# bot_schem_rev10_3.net
KiCad netlist of a schematic drawn in Altium Designer
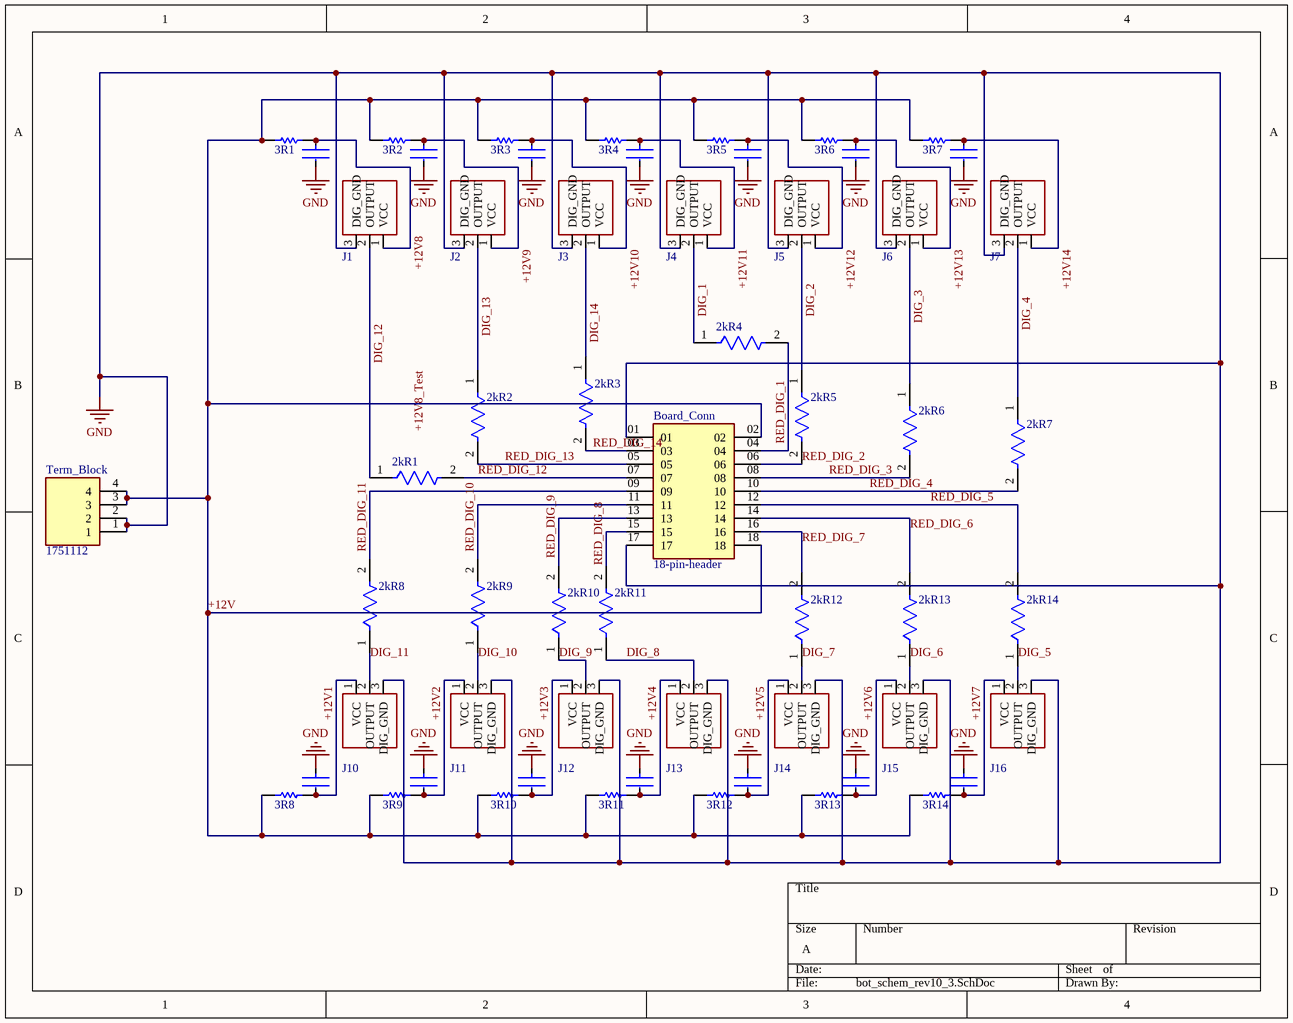
[diagram p0: bot_schem_rev10_3.SchDoc]

(export (version "E")
  (design (tool "Eeschema 10.0.6"))
  (components
    (comp (ref "2kR1")
      (value "CRCW06031K80FKEA")
      (footprint "2kOhm")
      (description "Res Thick Film 0603 1.8K Ohm 1% 1/10W ±100ppm/°C Molded SMD Paper T/R")
      (fields (field (name "MANUFACTURER") "Vishay") (field (name "TOLERANCE") "1%"))
      (libsource (lib "bot_schlib") (part "CRCW06031K80FKEA"))
    )
    (comp (ref "2kR2")
      (value "CRCW06031K80FKEA")
      (footprint "2kOhm")
      (description "Res Thick Film 0603 1.8K Ohm 1% 1/10W ±100ppm/°C Molded SMD Paper T/R")
      (fields (field (name "MANUFACTURER") "Vishay") (field (name "TOLERANCE") "1%"))
      (libsource (lib "bot_schlib") (part "CRCW06031K80FKEA"))
    )
    (comp (ref "2kR3")
      (value "CRCW06031K80FKEA")
      (footprint "2kOhm")
      (description "Res Thick Film 0603 1.8K Ohm 1% 1/10W ±100ppm/°C Molded SMD Paper T/R")
      (fields (field (name "MANUFACTURER") "Vishay") (field (name "TOLERANCE") "1%"))
      (libsource (lib "bot_schlib") (part "CRCW06031K80FKEA"))
    )
    (comp (ref "2kR4")
      (value "CRCW06031K80FKEA")
      (footprint "2kOhm")
      (description "Res Thick Film 0603 1.8K Ohm 1% 1/10W ±100ppm/°C Molded SMD Paper T/R")
      (fields (field (name "MANUFACTURER") "Vishay") (field (name "TOLERANCE") "1%"))
      (libsource (lib "bot_schlib") (part "CRCW06031K80FKEA"))
    )
    (comp (ref "2kR5")
      (value "CRCW06031K80FKEA")
      (footprint "2kOhm")
      (description "Res Thick Film 0603 1.8K Ohm 1% 1/10W ±100ppm/°C Molded SMD Paper T/R")
      (fields (field (name "MANUFACTURER") "Vishay") (field (name "TOLERANCE") "1%"))
      (libsource (lib "bot_schlib") (part "CRCW06031K80FKEA"))
    )
    (comp (ref "2kR6")
      (value "CRCW06031K80FKEA")
      (footprint "2kOhm")
      (description "Res Thick Film 0603 1.8K Ohm 1% 1/10W ±100ppm/°C Molded SMD Paper T/R")
      (fields (field (name "MANUFACTURER") "Vishay") (field (name "TOLERANCE") "1%"))
      (libsource (lib "bot_schlib") (part "CRCW06031K80FKEA"))
    )
    (comp (ref "2kR7")
      (value "CRCW06031K80FKEA")
      (footprint "2kOhm")
      (description "Res Thick Film 0603 1.8K Ohm 1% 1/10W ±100ppm/°C Molded SMD Paper T/R")
      (fields (field (name "MANUFACTURER") "Vishay") (field (name "TOLERANCE") "1%"))
      (libsource (lib "bot_schlib") (part "CRCW06031K80FKEA"))
    )
    (comp (ref "2kR8")
      (value "CRCW06031K80FKEA")
      (footprint "2kOhm")
      (description "Res Thick Film 0603 1.8K Ohm 1% 1/10W ±100ppm/°C Molded SMD Paper T/R")
      (fields (field (name "MANUFACTURER") "Vishay") (field (name "TOLERANCE") "1%"))
      (libsource (lib "bot_schlib") (part "CRCW06031K80FKEA"))
    )
    (comp (ref "2kR9")
      (value "CRCW06031K80FKEA")
      (footprint "2kOhm")
      (description "Res Thick Film 0603 1.8K Ohm 1% 1/10W ±100ppm/°C Molded SMD Paper T/R")
      (fields (field (name "MANUFACTURER") "Vishay") (field (name "TOLERANCE") "1%"))
      (libsource (lib "bot_schlib") (part "CRCW06031K80FKEA"))
    )
    (comp (ref "2kR10")
      (value "CRCW06031K80FKEA")
      (footprint "2kOhm")
      (description "Res Thick Film 0603 1.8K Ohm 1% 1/10W ±100ppm/°C Molded SMD Paper T/R")
      (fields (field (name "MANUFACTURER") "Vishay") (field (name "TOLERANCE") "1%"))
      (libsource (lib "bot_schlib") (part "CRCW06031K80FKEA"))
    )
    (comp (ref "2kR11")
      (value "CRCW06031K80FKEA")
      (footprint "2kOhm")
      (description "Res Thick Film 0603 1.8K Ohm 1% 1/10W ±100ppm/°C Molded SMD Paper T/R")
      (fields (field (name "MANUFACTURER") "Vishay") (field (name "TOLERANCE") "1%"))
      (libsource (lib "bot_schlib") (part "CRCW06031K80FKEA"))
    )
    (comp (ref "2kR12")
      (value "CRCW06031K80FKEA")
      (footprint "2kOhm")
      (description "Res Thick Film 0603 1.8K Ohm 1% 1/10W ±100ppm/°C Molded SMD Paper T/R")
      (fields (field (name "MANUFACTURER") "Vishay") (field (name "TOLERANCE") "1%"))
      (libsource (lib "bot_schlib") (part "CRCW06031K80FKEA"))
    )
    (comp (ref "2kR13")
      (value "CRCW06031K80FKEA")
      (footprint "2kOhm")
      (description "Res Thick Film 0603 1.8K Ohm 1% 1/10W ±100ppm/°C Molded SMD Paper T/R")
      (fields (field (name "MANUFACTURER") "Vishay") (field (name "TOLERANCE") "1%"))
      (libsource (lib "bot_schlib") (part "CRCW06031K80FKEA"))
    )
    (comp (ref "2kR14")
      (value "CRCW06031K80FKEA")
      (footprint "2kOhm")
      (description "Res Thick Film 0603 1.8K Ohm 1% 1/10W ±100ppm/°C Molded SMD Paper T/R")
      (fields (field (name "MANUFACTURER") "Vishay") (field (name "TOLERANCE") "1%"))
      (libsource (lib "bot_schlib") (part "CRCW06031K80FKEA"))
    )
    (comp (ref "3R1")
      (value "ERJ-8GEYJ3R0V")
      (footprint "3 ohm")
      (description "Res Thick Film 1206 3 Ohm 5% 1/4W -100ppm/C to 600ppm/C Molded SMD Punched Carrier T/R")
      (fields (field (name "MANUFACTURER") "Panasonic") (field (name "TOLERANCE") "5%"))
      (libsource (lib "bot_schlib") (part "ERJ-8GEYJ3R0V"))
    )
    (comp (ref "3R2")
      (value "ERJ-8GEYJ3R0V")
      (footprint "3 ohm")
      (description "Res Thick Film 1206 3 Ohm 5% 1/4W -100ppm/C to 600ppm/C Molded SMD Punched Carrier T/R")
      (fields (field (name "MANUFACTURER") "Panasonic") (field (name "TOLERANCE") "5%"))
      (libsource (lib "bot_schlib") (part "ERJ-8GEYJ3R0V"))
    )
    (comp (ref "3R3")
      (value "ERJ-8GEYJ3R0V")
      (footprint "3 ohm")
      (description "Res Thick Film 1206 3 Ohm 5% 1/4W -100ppm/C to 600ppm/C Molded SMD Punched Carrier T/R")
      (fields (field (name "MANUFACTURER") "Panasonic") (field (name "TOLERANCE") "5%"))
      (libsource (lib "bot_schlib") (part "ERJ-8GEYJ3R0V"))
    )
    (comp (ref "3R4")
      (value "ERJ-8GEYJ3R0V")
      (footprint "3 ohm")
      (description "Res Thick Film 1206 3 Ohm 5% 1/4W -100ppm/C to 600ppm/C Molded SMD Punched Carrier T/R")
      (fields (field (name "MANUFACTURER") "Panasonic") (field (name "TOLERANCE") "5%"))
      (libsource (lib "bot_schlib") (part "ERJ-8GEYJ3R0V"))
    )
    (comp (ref "3R5")
      (value "ERJ-8GEYJ3R0V")
      (footprint "3 ohm")
      (description "Res Thick Film 1206 3 Ohm 5% 1/4W -100ppm/C to 600ppm/C Molded SMD Punched Carrier T/R")
      (fields (field (name "MANUFACTURER") "Panasonic") (field (name "TOLERANCE") "5%"))
      (libsource (lib "bot_schlib") (part "ERJ-8GEYJ3R0V"))
    )
    (comp (ref "3R6")
      (value "ERJ-8GEYJ3R0V")
      (footprint "3 ohm")
      (description "Res Thick Film 1206 3 Ohm 5% 1/4W -100ppm/C to 600ppm/C Molded SMD Punched Carrier T/R")
      (fields (field (name "MANUFACTURER") "Panasonic") (field (name "TOLERANCE") "5%"))
      (libsource (lib "bot_schlib") (part "ERJ-8GEYJ3R0V"))
    )
    (comp (ref "3R7")
      (value "ERJ-8GEYJ3R0V")
      (footprint "3 ohm")
      (description "Res Thick Film 1206 3 Ohm 5% 1/4W -100ppm/C to 600ppm/C Molded SMD Punched Carrier T/R")
      (fields (field (name "MANUFACTURER") "Panasonic") (field (name "TOLERANCE") "5%"))
      (libsource (lib "bot_schlib") (part "ERJ-8GEYJ3R0V"))
    )
    (comp (ref "3R8")
      (value "ERJ-8GEYJ3R0V")
      (footprint "3 ohm")
      (description "Res Thick Film 1206 3 Ohm 5% 1/4W -100ppm/C to 600ppm/C Molded SMD Punched Carrier T/R")
      (fields (field (name "MANUFACTURER") "Panasonic") (field (name "TOLERANCE") "5%"))
      (libsource (lib "bot_schlib") (part "ERJ-8GEYJ3R0V"))
    )
    (comp (ref "3R9")
      (value "ERJ-8GEYJ3R0V")
      (footprint "3 ohm")
      (description "Res Thick Film 1206 3 Ohm 5% 1/4W -100ppm/C to 600ppm/C Molded SMD Punched Carrier T/R")
      (fields (field (name "MANUFACTURER") "Panasonic") (field (name "TOLERANCE") "5%"))
      (libsource (lib "bot_schlib") (part "ERJ-8GEYJ3R0V"))
    )
    (comp (ref "3R10")
      (value "ERJ-8GEYJ3R0V")
      (footprint "3 ohm")
      (description "Res Thick Film 1206 3 Ohm 5% 1/4W -100ppm/C to 600ppm/C Molded SMD Punched Carrier T/R")
      (fields (field (name "MANUFACTURER") "Panasonic") (field (name "TOLERANCE") "5%"))
      (libsource (lib "bot_schlib") (part "ERJ-8GEYJ3R0V"))
    )
    (comp (ref "3R11")
      (value "ERJ-8GEYJ3R0V")
      (footprint "3 ohm")
      (description "Res Thick Film 1206 3 Ohm 5% 1/4W -100ppm/C to 600ppm/C Molded SMD Punched Carrier T/R")
      (fields (field (name "MANUFACTURER") "Panasonic") (field (name "TOLERANCE") "5%"))
      (libsource (lib "bot_schlib") (part "ERJ-8GEYJ3R0V"))
    )
    (comp (ref "3R12")
      (value "ERJ-8GEYJ3R0V")
      (footprint "3 ohm")
      (description "Res Thick Film 1206 3 Ohm 5% 1/4W -100ppm/C to 600ppm/C Molded SMD Punched Carrier T/R")
      (fields (field (name "MANUFACTURER") "Panasonic") (field (name "TOLERANCE") "5%"))
      (libsource (lib "bot_schlib") (part "ERJ-8GEYJ3R0V"))
    )
    (comp (ref "3R13")
      (value "ERJ-8GEYJ3R0V")
      (footprint "3 ohm")
      (description "Res Thick Film 1206 3 Ohm 5% 1/4W -100ppm/C to 600ppm/C Molded SMD Punched Carrier T/R")
      (fields (field (name "MANUFACTURER") "Panasonic") (field (name "TOLERANCE") "5%"))
      (libsource (lib "bot_schlib") (part "ERJ-8GEYJ3R0V"))
    )
    (comp (ref "3R14")
      (value "ERJ-8GEYJ3R0V")
      (footprint "3 ohm")
      (description "Res Thick Film 1206 3 Ohm 5% 1/4W -100ppm/C to 600ppm/C Molded SMD Punched Carrier T/R")
      (fields (field (name "MANUFACTURER") "Panasonic") (field (name "TOLERANCE") "5%"))
      (libsource (lib "bot_schlib") (part "ERJ-8GEYJ3R0V"))
    )
    (comp (ref "Board_Conn")
      (value "18-pin-header")
      (footprint "18 pin header")
      (libsource (lib "bot_schlib") (part "18-pin-header"))
    )
    (comp (ref "C1")
      (value "C0805C104K5RACTU")
      (footprint "100nF")
      (description "Cap Ceramic 0.1uF 50V X7R 10% SMD 2.0 x 1.2 mm 125 C Paper T/R")
      (fields (field (name "MANUFACTURER") "KEMET") (field (name "TOLERANCE") "10%"))
      (libsource (lib "bot_schlib") (part "C0805C104K5RACTU"))
    )
    (comp (ref "C2")
      (value "C0805C104K5RACTU")
      (footprint "100nF")
      (description "Cap Ceramic 0.1uF 50V X7R 10% SMD 2.0 x 1.2 mm 125 C Paper T/R")
      (fields (field (name "MANUFACTURER") "KEMET") (field (name "TOLERANCE") "10%"))
      (libsource (lib "bot_schlib") (part "C0805C104K5RACTU"))
    )
    (comp (ref "C3")
      (value "C0805C104K5RACTU")
      (footprint "100nF")
      (description "Cap Ceramic 0.1uF 50V X7R 10% SMD 2.0 x 1.2 mm 125 C Paper T/R")
      (fields (field (name "MANUFACTURER") "KEMET") (field (name "TOLERANCE") "10%"))
      (libsource (lib "bot_schlib") (part "C0805C104K5RACTU"))
    )
    (comp (ref "C4")
      (value "C0805C104K5RACTU")
      (footprint "100nF")
      (description "Cap Ceramic 0.1uF 50V X7R 10% SMD 2.0 x 1.2 mm 125 C Paper T/R")
      (fields (field (name "MANUFACTURER") "KEMET") (field (name "TOLERANCE") "10%"))
      (libsource (lib "bot_schlib") (part "C0805C104K5RACTU"))
    )
    (comp (ref "C5")
      (value "C0805C104K5RACTU")
      (footprint "100nF")
      (description "Cap Ceramic 0.1uF 50V X7R 10% SMD 2.0 x 1.2 mm 125 C Paper T/R")
      (fields (field (name "MANUFACTURER") "KEMET") (field (name "TOLERANCE") "10%"))
      (libsource (lib "bot_schlib") (part "C0805C104K5RACTU"))
    )
    (comp (ref "C6")
      (value "C0805C104K5RACTU")
      (footprint "100nF")
      (description "Cap Ceramic 0.1uF 50V X7R 10% SMD 2.0 x 1.2 mm 125 C Paper T/R")
      (fields (field (name "MANUFACTURER") "KEMET") (field (name "TOLERANCE") "10%"))
      (libsource (lib "bot_schlib") (part "C0805C104K5RACTU"))
    )
    (comp (ref "C7")
      (value "C0805C104K5RACTU")
      (footprint "100nF")
      (description "Cap Ceramic 0.1uF 50V X7R 10% SMD 2.0 x 1.2 mm 125 C Paper T/R")
      (fields (field (name "MANUFACTURER") "KEMET") (field (name "TOLERANCE") "10%"))
      (libsource (lib "bot_schlib") (part "C0805C104K5RACTU"))
    )
    (comp (ref "C8")
      (value "C0805C104K5RACTU")
      (footprint "100nF")
      (description "Cap Ceramic 0.1uF 50V X7R 10% SMD 2.0 x 1.2 mm 125 C Paper T/R")
      (fields (field (name "MANUFACTURER") "KEMET") (field (name "TOLERANCE") "10%"))
      (libsource (lib "bot_schlib") (part "C0805C104K5RACTU"))
    )
    (comp (ref "C9")
      (value "C0805C104K5RACTU")
      (footprint "100nF")
      (description "Cap Ceramic 0.1uF 50V X7R 10% SMD 2.0 x 1.2 mm 125 C Paper T/R")
      (fields (field (name "MANUFACTURER") "KEMET") (field (name "TOLERANCE") "10%"))
      (libsource (lib "bot_schlib") (part "C0805C104K5RACTU"))
    )
    (comp (ref "C10")
      (value "C0805C104K5RACTU")
      (footprint "100nF")
      (description "Cap Ceramic 0.1uF 50V X7R 10% SMD 2.0 x 1.2 mm 125 C Paper T/R")
      (fields (field (name "MANUFACTURER") "KEMET") (field (name "TOLERANCE") "10%"))
      (libsource (lib "bot_schlib") (part "C0805C104K5RACTU"))
    )
    (comp (ref "C11")
      (value "C0805C104K5RACTU")
      (footprint "100nF")
      (description "Cap Ceramic 0.1uF 50V X7R 10% SMD 2.0 x 1.2 mm 125 C Paper T/R")
      (fields (field (name "MANUFACTURER") "KEMET") (field (name "TOLERANCE") "10%"))
      (libsource (lib "bot_schlib") (part "C0805C104K5RACTU"))
    )
    (comp (ref "C12")
      (value "C0805C104K5RACTU")
      (footprint "100nF")
      (description "Cap Ceramic 0.1uF 50V X7R 10% SMD 2.0 x 1.2 mm 125 C Paper T/R")
      (fields (field (name "MANUFACTURER") "KEMET") (field (name "TOLERANCE") "10%"))
      (libsource (lib "bot_schlib") (part "C0805C104K5RACTU"))
    )
    (comp (ref "C13")
      (value "C0805C104K5RACTU")
      (footprint "100nF")
      (description "Cap Ceramic 0.1uF 50V X7R 10% SMD 2.0 x 1.2 mm 125 C Paper T/R")
      (fields (field (name "MANUFACTURER") "KEMET") (field (name "TOLERANCE") "10%"))
      (libsource (lib "bot_schlib") (part "C0805C104K5RACTU"))
    )
    (comp (ref "C14")
      (value "C0805C104K5RACTU")
      (footprint "100nF")
      (description "Cap Ceramic 0.1uF 50V X7R 10% SMD 2.0 x 1.2 mm 125 C Paper T/R")
      (fields (field (name "MANUFACTURER") "KEMET") (field (name "TOLERANCE") "10%"))
      (libsource (lib "bot_schlib") (part "C0805C104K5RACTU"))
    )
    (comp (ref "J1")
      (value "IF-D95T")
      (footprint "IF-D95")
      (description "DETECTOR PHOTOLOGIC TTL/CMOS")
      (fields (field (name "MANUFACTURER") "Industrial Fiber Optics"))
      (libsource (lib "bot_schlib") (part "IF-D95T"))
    )
    (comp (ref "J2")
      (value "IF-D95T")
      (footprint "IF-D95")
      (description "DETECTOR PHOTOLOGIC TTL/CMOS")
      (fields (field (name "MANUFACTURER") "Industrial Fiber Optics"))
      (libsource (lib "bot_schlib") (part "IF-D95T"))
    )
    (comp (ref "J3")
      (value "IF-D95T")
      (footprint "IF-D95")
      (description "DETECTOR PHOTOLOGIC TTL/CMOS")
      (fields (field (name "MANUFACTURER") "Industrial Fiber Optics"))
      (libsource (lib "bot_schlib") (part "IF-D95T"))
    )
    (comp (ref "J4")
      (value "IF-D95T")
      (footprint "IF-D95")
      (description "DETECTOR PHOTOLOGIC TTL/CMOS")
      (fields (field (name "MANUFACTURER") "Industrial Fiber Optics"))
      (libsource (lib "bot_schlib") (part "IF-D95T"))
    )
    (comp (ref "J5")
      (value "IF-D95T")
      (footprint "IF-D95")
      (description "DETECTOR PHOTOLOGIC TTL/CMOS")
      (fields (field (name "MANUFACTURER") "Industrial Fiber Optics"))
      (libsource (lib "bot_schlib") (part "IF-D95T"))
    )
    (comp (ref "J6")
      (value "IF-D95T")
      (footprint "IF-D95")
      (description "DETECTOR PHOTOLOGIC TTL/CMOS")
      (fields (field (name "MANUFACTURER") "Industrial Fiber Optics"))
      (libsource (lib "bot_schlib") (part "IF-D95T"))
    )
    (comp (ref "J7")
      (value "IF-D95T")
      (footprint "IF-D95")
      (description "DETECTOR PHOTOLOGIC TTL/CMOS")
      (fields (field (name "MANUFACTURER") "Industrial Fiber Optics"))
      (libsource (lib "bot_schlib") (part "IF-D95T"))
    )
    (comp (ref "J10")
      (value "IF-D95T")
      (footprint "IF-D95")
      (description "DETECTOR PHOTOLOGIC TTL/CMOS")
      (fields (field (name "MANUFACTURER") "Industrial Fiber Optics"))
      (libsource (lib "bot_schlib") (part "IF-D95T"))
    )
    (comp (ref "J11")
      (value "IF-D95T")
      (footprint "IF-D95")
      (description "DETECTOR PHOTOLOGIC TTL/CMOS")
      (fields (field (name "MANUFACTURER") "Industrial Fiber Optics"))
      (libsource (lib "bot_schlib") (part "IF-D95T"))
    )
    (comp (ref "J12")
      (value "IF-D95T")
      (footprint "IF-D95")
      (description "DETECTOR PHOTOLOGIC TTL/CMOS")
      (fields (field (name "MANUFACTURER") "Industrial Fiber Optics"))
      (libsource (lib "bot_schlib") (part "IF-D95T"))
    )
    (comp (ref "J13")
      (value "IF-D95T")
      (footprint "IF-D95")
      (description "DETECTOR PHOTOLOGIC TTL/CMOS")
      (fields (field (name "MANUFACTURER") "Industrial Fiber Optics"))
      (libsource (lib "bot_schlib") (part "IF-D95T"))
    )
    (comp (ref "J14")
      (value "IF-D95T")
      (footprint "IF-D95")
      (description "DETECTOR PHOTOLOGIC TTL/CMOS")
      (fields (field (name "MANUFACTURER") "Industrial Fiber Optics"))
      (libsource (lib "bot_schlib") (part "IF-D95T"))
    )
    (comp (ref "J15")
      (value "IF-D95T")
      (footprint "IF-D95")
      (description "DETECTOR PHOTOLOGIC TTL/CMOS")
      (fields (field (name "MANUFACTURER") "Industrial Fiber Optics"))
      (libsource (lib "bot_schlib") (part "IF-D95T"))
    )
    (comp (ref "J16")
      (value "IF-D95T")
      (footprint "IF-D95")
      (description "DETECTOR PHOTOLOGIC TTL/CMOS")
      (fields (field (name "MANUFACTURER") "Industrial Fiber Optics"))
      (libsource (lib "bot_schlib") (part "IF-D95T"))
    )
    (comp (ref "Term_Block")
      (value "1751112")
      (footprint "4-pin terminal HORIZONTAL")
      (libsource (lib "bot_schlib") (part "1751112"))
    )
  )
  (nets
    (net (code "1") (name "/+12V") (class "Default")
      (node (ref "3R1") (pin "1") (pinfunction "1_1") (pintype "passive"))
      (node (ref "3R10") (pin "1") (pinfunction "1_1") (pintype "passive"))
      (node (ref "3R11") (pin "1") (pinfunction "1_1") (pintype "passive"))
      (node (ref "3R12") (pin "1") (pinfunction "1_1") (pintype "passive"))
      (node (ref "3R13") (pin "1") (pinfunction "1_1") (pintype "passive"))
      (node (ref "3R14") (pin "1") (pinfunction "1_1") (pintype "passive"))
      (node (ref "3R2") (pin "1") (pinfunction "1_1") (pintype "passive"))
      (node (ref "3R3") (pin "1") (pinfunction "1_1") (pintype "passive"))
      (node (ref "3R4") (pin "1") (pinfunction "1_1") (pintype "passive"))
      (node (ref "3R5") (pin "1") (pinfunction "1_1") (pintype "passive"))
      (node (ref "3R6") (pin "1") (pinfunction "1_1") (pintype "passive"))
      (node (ref "3R7") (pin "1") (pinfunction "1_1") (pintype "passive"))
      (node (ref "3R8") (pin "1") (pinfunction "1_1") (pintype "passive"))
      (node (ref "3R9") (pin "1") (pinfunction "1_1") (pintype "passive"))
      (node (ref "Board_Conn") (pin "02") (pinfunction "02_02") (pintype "passive"))
      (node (ref "Board_Conn") (pin "18") (pinfunction "18_18") (pintype "passive"))
      (node (ref "Term_Block") (pin "3") (pinfunction "3_3") (pintype "passive"))
      (node (ref "Term_Block") (pin "4") (pinfunction "4_4") (pintype "passive"))
    )
    (net (code "2") (name "/+12V1") (class "Default")
      (node (ref "3R8") (pin "2") (pinfunction "2_2") (pintype "passive"))
      (node (ref "C8") (pin "2") (pinfunction "2_2") (pintype "passive"))
      (node (ref "J10") (pin "1") (pinfunction "VCC_1") (pintype "passive"))
    )
    (net (code "3") (name "/+12V2") (class "Default")
      (node (ref "3R9") (pin "2") (pinfunction "2_2") (pintype "passive"))
      (node (ref "C9") (pin "2") (pinfunction "2_2") (pintype "passive"))
      (node (ref "J11") (pin "1") (pinfunction "VCC_1") (pintype "passive"))
    )
    (net (code "4") (name "/+12V3") (class "Default")
      (node (ref "3R10") (pin "2") (pinfunction "2_2") (pintype "passive"))
      (node (ref "C10") (pin "2") (pinfunction "2_2") (pintype "passive"))
      (node (ref "J12") (pin "1") (pinfunction "VCC_1") (pintype "passive"))
    )
    (net (code "5") (name "/+12V4") (class "Default")
      (node (ref "3R11") (pin "2") (pinfunction "2_2") (pintype "passive"))
      (node (ref "C11") (pin "2") (pinfunction "2_2") (pintype "passive"))
      (node (ref "J13") (pin "1") (pinfunction "VCC_1") (pintype "passive"))
    )
    (net (code "6") (name "/+12V5") (class "Default")
      (node (ref "3R12") (pin "2") (pinfunction "2_2") (pintype "passive"))
      (node (ref "C12") (pin "2") (pinfunction "2_2") (pintype "passive"))
      (node (ref "J14") (pin "1") (pinfunction "VCC_1") (pintype "passive"))
    )
    (net (code "7") (name "/+12V6") (class "Default")
      (node (ref "3R13") (pin "2") (pinfunction "2_2") (pintype "passive"))
      (node (ref "C13") (pin "2") (pinfunction "2_2") (pintype "passive"))
      (node (ref "J15") (pin "1") (pinfunction "VCC_1") (pintype "passive"))
    )
    (net (code "8") (name "/+12V7") (class "Default")
      (node (ref "3R14") (pin "2") (pinfunction "2_2") (pintype "passive"))
      (node (ref "C14") (pin "2") (pinfunction "2_2") (pintype "passive"))
      (node (ref "J16") (pin "1") (pinfunction "VCC_1") (pintype "passive"))
    )
    (net (code "9") (name "/+12V8") (class "Default")
      (node (ref "3R1") (pin "2") (pinfunction "2_2") (pintype "passive"))
      (node (ref "C1") (pin "1") (pinfunction "1_1") (pintype "passive"))
      (node (ref "J1") (pin "1") (pinfunction "VCC_1") (pintype "passive"))
    )
    (net (code "11") (name "/+12V9") (class "Default")
      (node (ref "3R2") (pin "2") (pinfunction "2_2") (pintype "passive"))
      (node (ref "C2") (pin "1") (pinfunction "1_1") (pintype "passive"))
      (node (ref "J2") (pin "1") (pinfunction "VCC_1") (pintype "passive"))
    )
    (net (code "12") (name "/+12V10") (class "Default")
      (node (ref "3R3") (pin "2") (pinfunction "2_2") (pintype "passive"))
      (node (ref "C3") (pin "1") (pinfunction "1_1") (pintype "passive"))
      (node (ref "J3") (pin "1") (pinfunction "VCC_1") (pintype "passive"))
    )
    (net (code "13") (name "/+12V11") (class "Default")
      (node (ref "3R4") (pin "2") (pinfunction "2_2") (pintype "passive"))
      (node (ref "C4") (pin "1") (pinfunction "1_1") (pintype "passive"))
      (node (ref "J4") (pin "1") (pinfunction "VCC_1") (pintype "passive"))
    )
    (net (code "14") (name "/+12V12") (class "Default")
      (node (ref "3R5") (pin "2") (pinfunction "2_2") (pintype "passive"))
      (node (ref "C5") (pin "1") (pinfunction "1_1") (pintype "passive"))
      (node (ref "J5") (pin "1") (pinfunction "VCC_1") (pintype "passive"))
    )
    (net (code "15") (name "/+12V13") (class "Default")
      (node (ref "3R6") (pin "2") (pinfunction "2_2") (pintype "passive"))
      (node (ref "C6") (pin "1") (pinfunction "1_1") (pintype "passive"))
      (node (ref "J6") (pin "1") (pinfunction "VCC_1") (pintype "passive"))
    )
    (net (code "16") (name "/+12V14") (class "Default")
      (node (ref "3R7") (pin "2") (pinfunction "2_2") (pintype "passive"))
      (node (ref "C7") (pin "1") (pinfunction "1_1") (pintype "passive"))
      (node (ref "J7") (pin "1") (pinfunction "VCC_1") (pintype "passive"))
    )
    (net (code "17") (name "/DIG_1") (class "Default")
      (node (ref "2kR4") (pin "1") (pinfunction "1_1") (pintype "passive"))
      (node (ref "J4") (pin "2") (pinfunction "OUTPUT_2") (pintype "passive"))
    )
    (net (code "18") (name "/DIG_2") (class "Default")
      (node (ref "2kR5") (pin "1") (pinfunction "1_1") (pintype "passive"))
      (node (ref "J5") (pin "2") (pinfunction "OUTPUT_2") (pintype "passive"))
    )
    (net (code "19") (name "/DIG_3") (class "Default")
      (node (ref "2kR6") (pin "1") (pinfunction "1_1") (pintype "passive"))
      (node (ref "J6") (pin "2") (pinfunction "OUTPUT_2") (pintype "passive"))
    )
    (net (code "20") (name "/DIG_4") (class "Default")
      (node (ref "2kR7") (pin "1") (pinfunction "1_1") (pintype "passive"))
      (node (ref "J7") (pin "2") (pinfunction "OUTPUT_2") (pintype "passive"))
    )
    (net (code "24") (name "/DIG_8") (class "Default")
      (node (ref "2kR11") (pin "1") (pinfunction "1_1") (pintype "passive"))
      (node (ref "J13") (pin "2") (pinfunction "OUTPUT_2") (pintype "passive"))
    )
    (net (code "25") (name "/DIG_9") (class "Default")
      (node (ref "2kR10") (pin "1") (pinfunction "1_1") (pintype "passive"))
      (node (ref "J12") (pin "2") (pinfunction "OUTPUT_2") (pintype "passive"))
    )
    (net (code "26") (name "/DIG_10") (class "Default")
      (node (ref "2kR9") (pin "1") (pinfunction "1_1") (pintype "passive"))
      (node (ref "J11") (pin "2") (pinfunction "OUTPUT_2") (pintype "passive"))
    )
    (net (code "27") (name "/DIG_11") (class "Default")
      (node (ref "2kR8") (pin "1") (pinfunction "1_1") (pintype "passive"))
      (node (ref "J10") (pin "2") (pinfunction "OUTPUT_2") (pintype "passive"))
    )
    (net (code "28") (name "/DIG_12") (class "Default")
      (node (ref "2kR1") (pin "1") (pinfunction "1_1") (pintype "passive"))
      (node (ref "J1") (pin "2") (pinfunction "OUTPUT_2") (pintype "passive"))
    )
    (net (code "29") (name "/DIG_13") (class "Default")
      (node (ref "2kR2") (pin "1") (pinfunction "1_1") (pintype "passive"))
      (node (ref "J2") (pin "2") (pinfunction "OUTPUT_2") (pintype "passive"))
    )
    (net (code "30") (name "/DIG_14") (class "Default")
      (node (ref "2kR3") (pin "1") (pinfunction "1_1") (pintype "passive"))
      (node (ref "J3") (pin "2") (pinfunction "OUTPUT_2") (pintype "passive"))
    )
    (net (code "31") (name "/RED_DIG_1") (class "Default")
      (node (ref "2kR4") (pin "2") (pinfunction "2_2") (pintype "passive"))
      (node (ref "Board_Conn") (pin "04") (pinfunction "04_04") (pintype "passive"))
    )
    (net (code "32") (name "/RED_DIG_2") (class "Default")
      (node (ref "2kR5") (pin "2") (pinfunction "2_2") (pintype "passive"))
      (node (ref "Board_Conn") (pin "06") (pinfunction "06_06") (pintype "passive"))
    )
    (net (code "33") (name "/RED_DIG_3") (class "Default")
      (node (ref "2kR6") (pin "2") (pinfunction "2_2") (pintype "passive"))
      (node (ref "Board_Conn") (pin "08") (pinfunction "08_08") (pintype "passive"))
    )
    (net (code "34") (name "/RED_DIG_4") (class "Default")
      (node (ref "2kR7") (pin "2") (pinfunction "2_2") (pintype "passive"))
      (node (ref "Board_Conn") (pin "10") (pinfunction "10_10") (pintype "passive"))
    )
    (net (code "35") (name "/RED_DIG_5") (class "Default")
      (node (ref "2kR14") (pin "2") (pinfunction "2_2") (pintype "passive"))
      (node (ref "Board_Conn") (pin "12") (pinfunction "12_12") (pintype "passive"))
    )
    (net (code "36") (name "/RED_DIG_6") (class "Default")
      (node (ref "2kR13") (pin "2") (pinfunction "2_2") (pintype "passive"))
      (node (ref "Board_Conn") (pin "14") (pinfunction "14_14") (pintype "passive"))
    )
    (net (code "37") (name "/RED_DIG_7") (class "Default")
      (node (ref "2kR12") (pin "2") (pinfunction "2_2") (pintype "passive"))
      (node (ref "Board_Conn") (pin "16") (pinfunction "16_16") (pintype "passive"))
    )
    (net (code "38") (name "/RED_DIG_8") (class "Default")
      (node (ref "2kR11") (pin "2") (pinfunction "2_2") (pintype "passive"))
      (node (ref "Board_Conn") (pin "15") (pinfunction "15_15") (pintype "passive"))
    )
    (net (code "39") (name "/RED_DIG_9") (class "Default")
      (node (ref "2kR10") (pin "2") (pinfunction "2_2") (pintype "passive"))
      (node (ref "Board_Conn") (pin "13") (pinfunction "13_13") (pintype "passive"))
    )
    (net (code "40") (name "/RED_DIG_10") (class "Default")
      (node (ref "2kR9") (pin "2") (pinfunction "2_2") (pintype "passive"))
      (node (ref "Board_Conn") (pin "11") (pinfunction "11_11") (pintype "passive"))
    )
    (net (code "41") (name "/RED_DIG_11") (class "Default")
      (node (ref "2kR8") (pin "2") (pinfunction "2_2") (pintype "passive"))
      (node (ref "Board_Conn") (pin "09") (pinfunction "09_09") (pintype "passive"))
    )
    (net (code "42") (name "/RED_DIG_12") (class "Default")
      (node (ref "2kR1") (pin "2") (pinfunction "2_2") (pintype "passive"))
      (node (ref "Board_Conn") (pin "07") (pinfunction "07_07") (pintype "passive"))
    )
    (net (code "43") (name "/RED_DIG_13") (class "Default")
      (node (ref "2kR2") (pin "2") (pinfunction "2_2") (pintype "passive"))
      (node (ref "Board_Conn") (pin "05") (pinfunction "05_05") (pintype "passive"))
    )
    (net (code "44") (name "/RED_DIG_14") (class "Default")
      (node (ref "2kR3") (pin "2") (pinfunction "2_2") (pintype "passive"))
      (node (ref "Board_Conn") (pin "03") (pinfunction "03_03") (pintype "passive"))
    )
    (net (code "45") (name "GND") (class "Default")
      (node (ref "Board_Conn") (pin "01") (pinfunction "01_01") (pintype "passive"))
      (node (ref "Board_Conn") (pin "17") (pinfunction "17_17") (pintype "passive"))
      (node (ref "C1") (pin "2") (pinfunction "2_2") (pintype "passive"))
      (node (ref "C10") (pin "1") (pinfunction "1_1") (pintype "passive"))
      (node (ref "C11") (pin "1") (pinfunction "1_1") (pintype "passive"))
      (node (ref "C12") (pin "1") (pinfunction "1_1") (pintype "passive"))
      (node (ref "C13") (pin "1") (pinfunction "1_1") (pintype "passive"))
      (node (ref "C14") (pin "1") (pinfunction "1_1") (pintype "passive"))
      (node (ref "C2") (pin "2") (pinfunction "2_2") (pintype "passive"))
      (node (ref "C3") (pin "2") (pinfunction "2_2") (pintype "passive"))
      (node (ref "C4") (pin "2") (pinfunction "2_2") (pintype "passive"))
      (node (ref "C5") (pin "2") (pinfunction "2_2") (pintype "passive"))
      (node (ref "C6") (pin "2") (pinfunction "2_2") (pintype "passive"))
      (node (ref "C7") (pin "2") (pinfunction "2_2") (pintype "passive"))
      (node (ref "C8") (pin "1") (pinfunction "1_1") (pintype "passive"))
      (node (ref "C9") (pin "1") (pinfunction "1_1") (pintype "passive"))
      (node (ref "J1") (pin "3") (pinfunction "DIG_GND_3") (pintype "passive"))
      (node (ref "J10") (pin "3") (pinfunction "DIG_GND_3") (pintype "passive"))
      (node (ref "J11") (pin "3") (pinfunction "DIG_GND_3") (pintype "passive"))
      (node (ref "J12") (pin "3") (pinfunction "DIG_GND_3") (pintype "passive"))
      (node (ref "J13") (pin "3") (pinfunction "DIG_GND_3") (pintype "passive"))
      (node (ref "J14") (pin "3") (pinfunction "DIG_GND_3") (pintype "passive"))
      (node (ref "J15") (pin "3") (pinfunction "DIG_GND_3") (pintype "passive"))
      (node (ref "J16") (pin "3") (pinfunction "DIG_GND_3") (pintype "passive"))
      (node (ref "J2") (pin "3") (pinfunction "DIG_GND_3") (pintype "passive"))
      (node (ref "J3") (pin "3") (pinfunction "DIG_GND_3") (pintype "passive"))
      (node (ref "J4") (pin "3") (pinfunction "DIG_GND_3") (pintype "passive"))
      (node (ref "J5") (pin "3") (pinfunction "DIG_GND_3") (pintype "passive"))
      (node (ref "J6") (pin "3") (pinfunction "DIG_GND_3") (pintype "passive"))
      (node (ref "J7") (pin "3") (pinfunction "DIG_GND_3") (pintype "passive"))
      (node (ref "Term_Block") (pin "1") (pinfunction "1_1") (pintype "passive"))
      (node (ref "Term_Block") (pin "2") (pinfunction "2_2") (pintype "passive"))
    )
    (net (code "46") (name "Net-(J14-OUTPUT)") (class "Default")
      (node (ref "2kR12") (pin "1") (pinfunction "1_1") (pintype "passive"))
      (node (ref "J14") (pin "2") (pinfunction "OUTPUT_2") (pintype "passive"))
    )
    (net (code "47") (name "Net-(J15-OUTPUT)") (class "Default")
      (node (ref "2kR13") (pin "1") (pinfunction "1_1") (pintype "passive"))
      (node (ref "J15") (pin "2") (pinfunction "OUTPUT_2") (pintype "passive"))
    )
    (net (code "48") (name "Net-(J16-OUTPUT)") (class "Default")
      (node (ref "2kR14") (pin "1") (pinfunction "1_1") (pintype "passive"))
      (node (ref "J16") (pin "2") (pinfunction "OUTPUT_2") (pintype "passive"))
    )
  )
)
